# LED_Indicator.net
KiCad netlist of a schematic drawn in Altium Designer
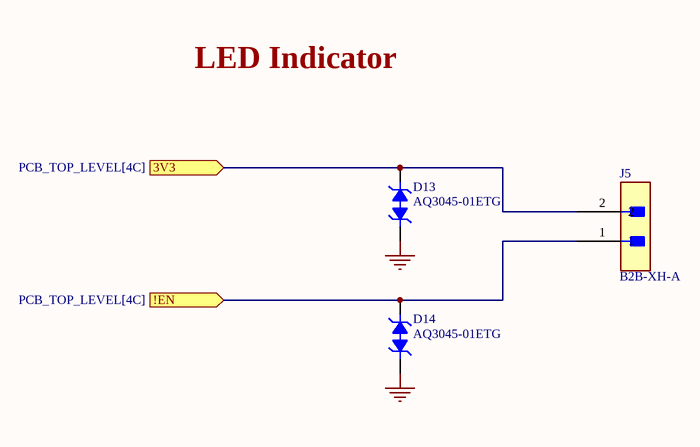
[diagram p0: LED_Indicator.SchDoc]

(export (version "E")
  (design (tool "Eeschema 10.0.6"))
  (components
    (comp (ref "D13")
      (value "AQ3045-01ETG")
      (footprint "SOD882")
      (description "TVS DIODE 5.3VWM 12VC SOD882")
      (fields (field (name "MANUFACTURER") "Littelfuse") (field (name "LCSC PART NUMBER") "C3710326"))
      (libsource (lib "Schlib") (part "AQ3045-01ETG"))
    )
    (comp (ref "D14")
      (value "AQ3045-01ETG")
      (footprint "SOD882")
      (description "TVS DIODE 5.3VWM 12VC SOD882")
      (fields (field (name "MANUFACTURER") "Littelfuse") (field (name "LCSC PART NUMBER") "C3710326"))
      (libsource (lib "Schlib") (part "AQ3045-01ETG"))
    )
    (comp (ref "J5")
      (value "B2B-XH-A")
      (footprint "CONN_B2B-XH-A_JST")
      (description "Board Connector, 2 Contact(s), 1 Row(s), Male, Straight, Solder Terminal")
      (fields (field (name "MANUFACTURER") "JST"))
      (libsource (lib "Schlib") (part "B2B-XH-A"))
    )
  )
  (nets
    (net (code "1") (name "/!EN") (class "Default")
      (node (ref "D14") (pin "2") (pinfunction "2_2") (pintype "passive"))
      (node (ref "J5") (pin "1") (pinfunction "1_1") (pintype "passive"))
    )
    (net (code "2") (name "/3V3") (class "Default")
      (node (ref "D13") (pin "2") (pinfunction "2_2") (pintype "passive"))
      (node (ref "J5") (pin "2") (pinfunction "2_2") (pintype "passive"))
    )
    (net (code "3") (name "GND") (class "Default")
      (node (ref "D13") (pin "1") (pinfunction "1_1") (pintype "passive"))
      (node (ref "D14") (pin "1") (pinfunction "1_1") (pintype "passive"))
    )
  )
)
